# Serial-Basic-CH340C.net
KiCad netlist of a schematic drawn in EAGLE
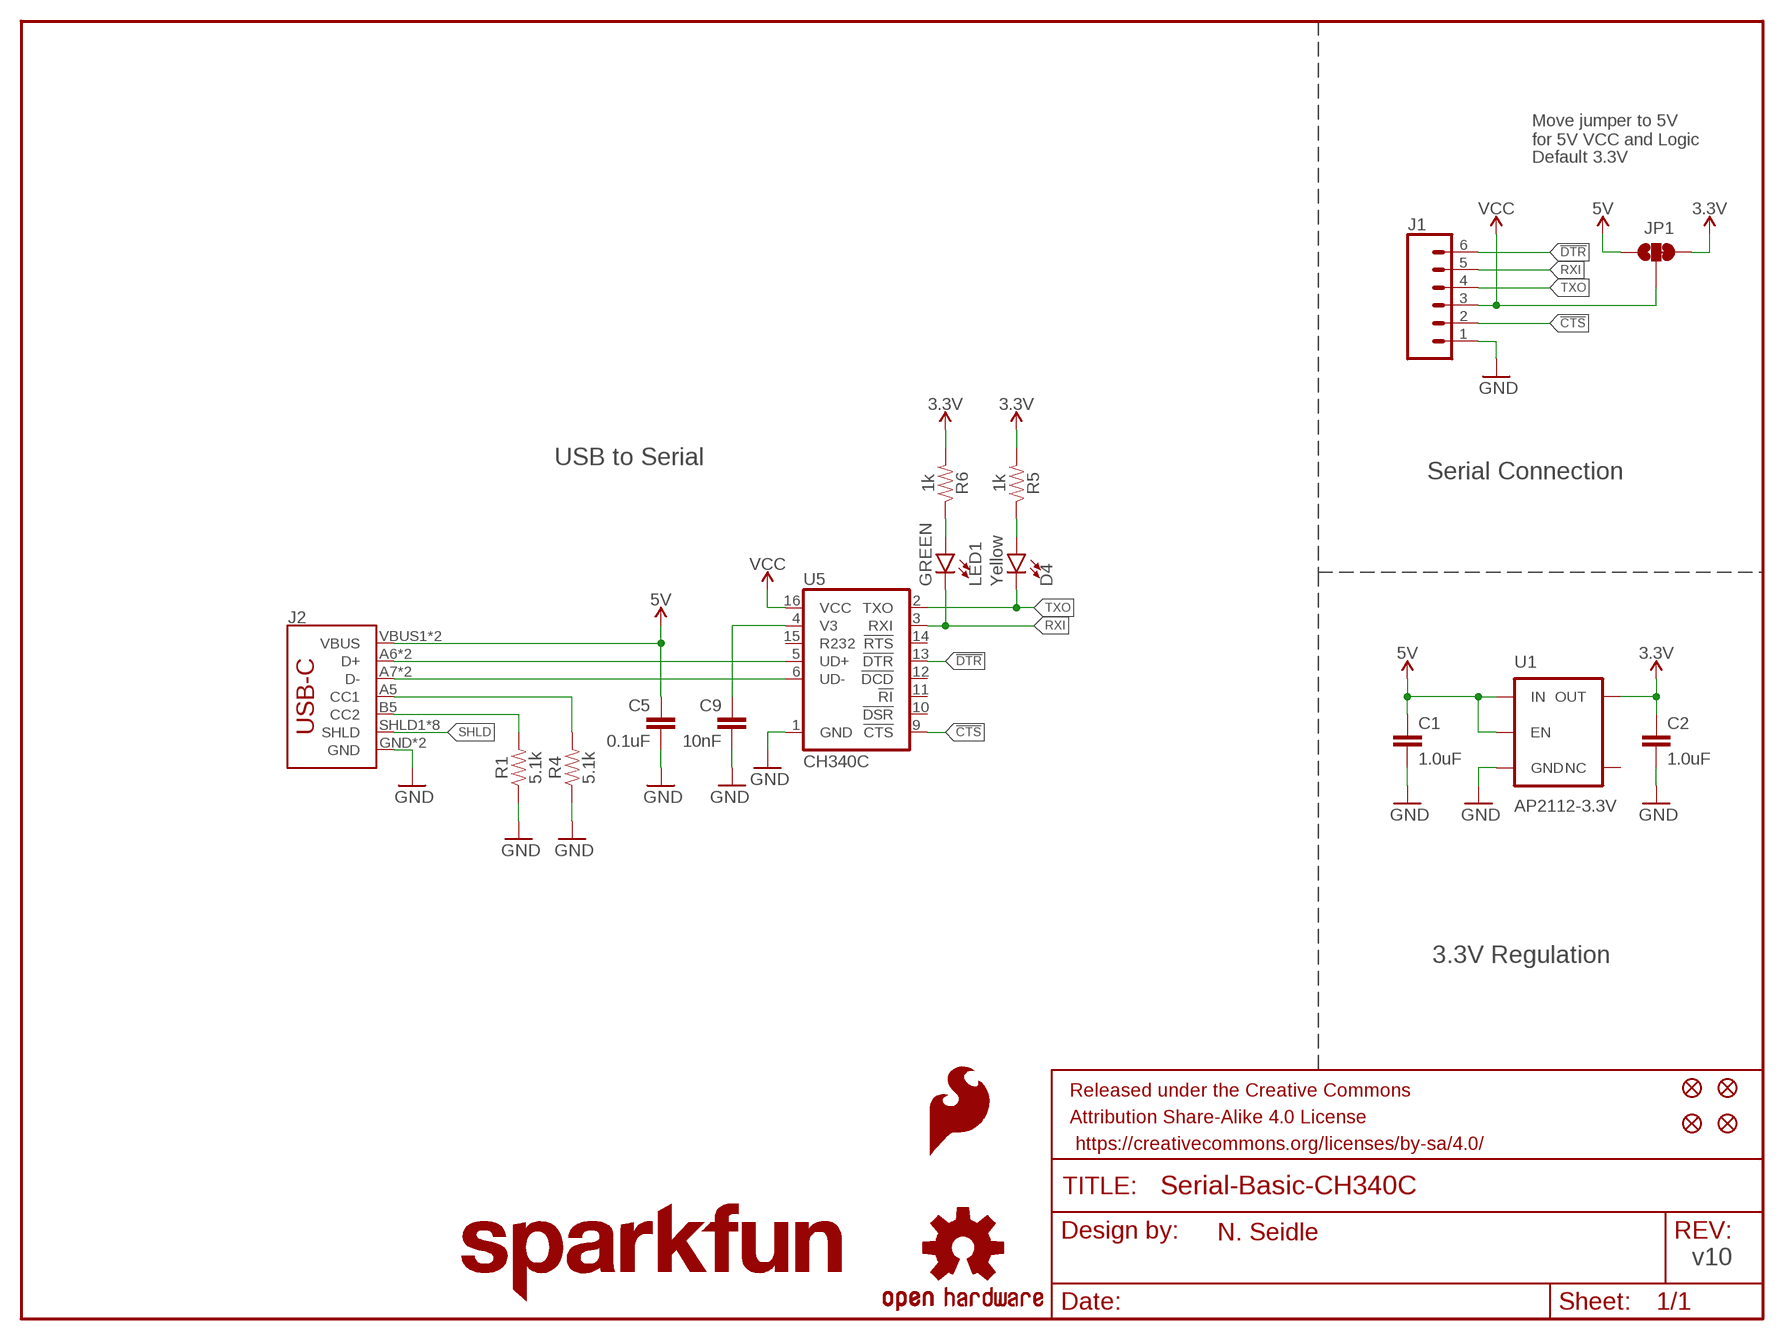
[diagram p0: schematic, sheet 1]

(export (version "E")
  (design (tool "Eeschema 10.0.6"))
  (components
    (comp (ref "C1")
      (value "1.0uF")
      (footprint "eagle-import:0603")
      (libsource (lib "eagle-import") (part "1.0UF-0603-16V-10%"))
    )
    (comp (ref "C2")
      (value "1.0uF")
      (footprint "eagle-import:0603")
      (libsource (lib "eagle-import") (part "1.0UF-0603-16V-10%"))
    )
    (comp (ref "C5")
      (value "0.1uF")
      (footprint "eagle-import:0603")
      (libsource (lib "eagle-import") (part "0.1UF-0603-25V-(+80/-20%)"))
    )
    (comp (ref "C9")
      (value "10nF")
      (footprint "eagle-import:0603")
      (libsource (lib "eagle-import") (part "10NF-0603-50V-10%"))
    )
    (comp (ref "D4")
      (value "Yellow")
      (footprint "eagle-import:LED-0603")
      (libsource (lib "eagle-import") (part "LED-YELLOW0603"))
    )
    (comp (ref "FRAME1")
      (value "FRAME-LETTER")
      (footprint "eagle-import:CREATIVE_COMMONS")
      (libsource (lib "eagle-import") (part "FRAME-LETTER"))
    )
    (comp (ref "J1")
      (value "CONN_06SMD-FEMALE-V2")
      (footprint "eagle-import:1X06-SMD-FEMALE")
      (libsource (lib "eagle-import") (part "CONN_06SMD-FEMALE-V2"))
    )
    (comp (ref "J2")
      (value "USB_C16PIN")
      (footprint "eagle-import:USB-C-16P")
      (libsource (lib "eagle-import") (part "USB_C16PIN"))
    )
    (comp (ref "JP1")
      (value "JUMPER-SMT_3_1-NC_TRACE_SILK")
      (footprint "eagle-import:SMT-JUMPER_3_1-NC_TRACE_SILK")
      (libsource (lib "eagle-import") (part "JUMPER-SMT_3_1-NC_TRACE_SILK"))
    )
    (comp (ref "JP3")
      (value "FIDUCIAL1X2")
      (footprint "eagle-import:FIDUCIAL-1X2")
      (libsource (lib "eagle-import") (part "FIDUCIAL1X2"))
    )
    (comp (ref "JP4")
      (value "FIDUCIAL1X2")
      (footprint "eagle-import:FIDUCIAL-1X2")
      (libsource (lib "eagle-import") (part "FIDUCIAL1X2"))
    )
    (comp (ref "JP5")
      (value "FIDUCIAL1X2")
      (footprint "eagle-import:FIDUCIAL-1X2")
      (libsource (lib "eagle-import") (part "FIDUCIAL1X2"))
    )
    (comp (ref "JP6")
      (value "FIDUCIAL1X2")
      (footprint "eagle-import:FIDUCIAL-1X2")
      (libsource (lib "eagle-import") (part "FIDUCIAL1X2"))
    )
    (comp (ref "LED1")
      (value "GREEN")
      (footprint "eagle-import:LED-0603")
      (libsource (lib "eagle-import") (part "LED-GREEN0603"))
    )
    (comp (ref "LOGO1")
      (value "OSHW-LOGOS")
      (footprint "eagle-import:OSHW-LOGO-S")
      (libsource (lib "eagle-import") (part "OSHW-LOGOS"))
    )
    (comp (ref "LOGO2")
      (value "SFE_LOGO_FLAME.1_INCH")
      (footprint "eagle-import:SFE_LOGO_FLAME_.1")
      (libsource (lib "eagle-import") (part "SFE_LOGO_FLAME.1_INCH"))
    )
    (comp (ref "LOGO3")
      (value "SFE_LOGO_NAME.1_INCH")
      (footprint "eagle-import:SFE_LOGO_NAME_.1")
      (libsource (lib "eagle-import") (part "SFE_LOGO_NAME.1_INCH"))
    )
    (comp (ref "R1")
      (value "5.1k")
      (footprint "eagle-import:0603")
      (libsource (lib "eagle-import") (part "5.1KOHM5.1KOHM-0603-1/10W-1%"))
    )
    (comp (ref "R4")
      (value "5.1k")
      (footprint "eagle-import:0603")
      (libsource (lib "eagle-import") (part "5.1KOHM5.1KOHM-0603-1/10W-1%"))
    )
    (comp (ref "R5")
      (value "1k")
      (footprint "eagle-import:0603")
      (libsource (lib "eagle-import") (part "1KOHM-0603-1/10W-1%"))
    )
    (comp (ref "R6")
      (value "1k")
      (footprint "eagle-import:0603")
      (libsource (lib "eagle-import") (part "1KOHM-0603-1/10W-1%"))
    )
    (comp (ref "U1")
      (value "AP2112-3.3V")
      (footprint "eagle-import:SOT23-5")
      (libsource (lib "eagle-import") (part "V_REG_AP2112K-3.3V"))
    )
    (comp (ref "U5")
      (value "CH340C")
      (footprint "eagle-import:SO016")
      (libsource (lib "eagle-import") (part "CH340C"))
    )
  )
  (nets
    (net (code "1") (name "/~{CTS}") (class "Default")
      (node (ref "J1") (pin "2") (pinfunction "2_2") (pintype "passive"))
      (node (ref "U5") (pin "9") (pinfunction "~{CTS}_9") (pintype "bidirectional"))
    )
    (net (code "2") (name "/~{DTR}") (class "Default")
      (node (ref "J1") (pin "6") (pinfunction "6_6") (pintype "passive"))
      (node (ref "U5") (pin "13") (pinfunction "~{DTR}_13") (pintype "bidirectional"))
    )
    (net (code "3") (name "3.3V") (class "Default")
      (node (ref "C2") (pin "1") (pinfunction "1_1") (pintype "passive"))
      (node (ref "JP1") (pin "3") (pinfunction "3_3") (pintype "passive"))
      (node (ref "R5") (pin "2") (pinfunction "2_2") (pintype "passive"))
      (node (ref "R6") (pin "2") (pinfunction "2_2") (pintype "passive"))
      (node (ref "U1") (pin "5") (pinfunction "OUT_5") (pintype "passive"))
    )
    (net (code "4") (name "5V") (class "Default")
      (node (ref "C1") (pin "1") (pinfunction "1_1") (pintype "passive"))
      (node (ref "C5") (pin "1") (pinfunction "1_1") (pintype "passive"))
      (node (ref "J2") (pin "VBUS1") (pinfunction "VBUS_VBUS1") (pintype "bidirectional"))
      (node (ref "J2") (pin "VBUS2") (pinfunction "VBUS_VBUS2") (pintype "bidirectional"))
      (node (ref "JP1") (pin "1") (pinfunction "1_1") (pintype "passive"))
      (node (ref "U1") (pin "1") (pinfunction "IN_1") (pintype "input"))
      (node (ref "U1") (pin "3") (pinfunction "EN_3") (pintype "input"))
    )
    (net (code "5") (name "GND") (class "Default")
      (node (ref "C1") (pin "2") (pinfunction "2_2") (pintype "passive"))
      (node (ref "C2") (pin "2") (pinfunction "2_2") (pintype "passive"))
      (node (ref "C5") (pin "2") (pinfunction "2_2") (pintype "passive"))
      (node (ref "C9") (pin "2") (pinfunction "2_2") (pintype "passive"))
      (node (ref "J1") (pin "1") (pinfunction "1_1") (pintype "passive"))
      (node (ref "J2") (pin "GND") (pinfunction "GND_GND") (pintype "bidirectional"))
      (node (ref "J2") (pin "GND2") (pinfunction "GND_GND2") (pintype "bidirectional"))
      (node (ref "R1") (pin "1") (pinfunction "1_1") (pintype "passive"))
      (node (ref "R4") (pin "1") (pinfunction "1_1") (pintype "passive"))
      (node (ref "U1") (pin "2") (pinfunction "GND_2") (pintype "input"))
      (node (ref "U5") (pin "1") (pinfunction "GND_1") (pintype "bidirectional"))
    )
    (net (code "6") (name "Net-(D4-PadA)") (class "Default")
      (node (ref "D4") (pin "A") (pinfunction "A_A") (pintype "passive"))
      (node (ref "R5") (pin "1") (pinfunction "1_1") (pintype "passive"))
    )
    (net (code "7") (name "Net-(J2-CC1)") (class "Default")
      (node (ref "J2") (pin "A5") (pinfunction "CC1_A5") (pintype "bidirectional"))
      (node (ref "R4") (pin "2") (pinfunction "2_2") (pintype "passive"))
    )
    (net (code "8") (name "Net-(J2-CC2)") (class "Default")
      (node (ref "J2") (pin "B5") (pinfunction "CC2_B5") (pintype "bidirectional"))
      (node (ref "R1") (pin "2") (pinfunction "2_2") (pintype "passive"))
    )
    (net (code "9") (name "Net-(LED1-PadA)") (class "Default")
      (node (ref "LED1") (pin "A") (pinfunction "A_A") (pintype "passive"))
      (node (ref "R6") (pin "1") (pinfunction "1_1") (pintype "passive"))
    )
    (net (code "10") (name "Net-(U5-UD+)") (class "Default")
      (node (ref "J2") (pin "A6") (pinfunction "D+_A6") (pintype "bidirectional"))
      (node (ref "J2") (pin "B6") (pinfunction "D+_B6") (pintype "bidirectional"))
      (node (ref "U5") (pin "5") (pinfunction "UD+_5") (pintype "bidirectional"))
    )
    (net (code "11") (name "Net-(U5-UD-)") (class "Default")
      (node (ref "J2") (pin "A7") (pinfunction "D-_A7") (pintype "bidirectional"))
      (node (ref "J2") (pin "B7") (pinfunction "D-_B7") (pintype "bidirectional"))
      (node (ref "U5") (pin "6") (pinfunction "UD-_6") (pintype "bidirectional"))
    )
    (net (code "12") (name "Net-(U5-V3)") (class "Default")
      (node (ref "C9") (pin "1") (pinfunction "1_1") (pintype "passive"))
      (node (ref "U5") (pin "4") (pinfunction "V3_4") (pintype "bidirectional"))
    )
    (net (code "13") (name "RXI") (class "Default")
      (node (ref "J1") (pin "5") (pinfunction "5_5") (pintype "passive"))
      (node (ref "LED1") (pin "C") (pinfunction "C_C") (pintype "passive"))
      (node (ref "U5") (pin "3") (pinfunction "RXI_3") (pintype "bidirectional"))
    )
    (net (code "14") (name "SHLD") (class "Default")
      (node (ref "J2") (pin "SHLD1") (pinfunction "SHLD_SHLD1") (pintype "bidirectional"))
      (node (ref "J2") (pin "SHLD2") (pinfunction "SHLD_SHLD2") (pintype "bidirectional"))
      (node (ref "J2") (pin "SHLD3") (pinfunction "SHLD_SHLD3") (pintype "bidirectional"))
      (node (ref "J2") (pin "SHLD4") (pinfunction "SHLD_SHLD4") (pintype "bidirectional"))
      (node (ref "J2") (pin "SHLD5") (pinfunction "SHLD_SHLD5") (pintype "bidirectional"))
      (node (ref "J2") (pin "SHLD6") (pinfunction "SHLD_SHLD6") (pintype "bidirectional"))
      (node (ref "J2") (pin "SHLD7") (pinfunction "SHLD_SHLD7") (pintype "bidirectional"))
      (node (ref "J2") (pin "SHLD8") (pinfunction "SHLD_SHLD8") (pintype "bidirectional"))
    )
    (net (code "15") (name "TXO") (class "Default")
      (node (ref "D4") (pin "C") (pinfunction "C_C") (pintype "passive"))
      (node (ref "J1") (pin "4") (pinfunction "4_4") (pintype "passive"))
      (node (ref "U5") (pin "2") (pinfunction "TXO_2") (pintype "bidirectional"))
    )
    (net (code "16") (name "VCC") (class "Default")
      (node (ref "J1") (pin "3") (pinfunction "3_3") (pintype "passive"))
      (node (ref "JP1") (pin "2") (pinfunction "2_2") (pintype "passive"))
      (node (ref "U5") (pin "16") (pinfunction "VCC_16") (pintype "bidirectional"))
    )
    (net (code "17") (name "unconnected-(U1-NC-Pad4)") (class "Default")
      (node (ref "U1") (pin "4") (pinfunction "NC_4") (pintype "input"))
    )
    (net (code "18") (name "unconnected-(U5-R232-Pad15)") (class "Default")
      (node (ref "U5") (pin "15") (pinfunction "R232_15") (pintype "bidirectional"))
    )
    (net (code "19") (name "unconnected-(U5-~{DCD}-Pad12)") (class "Default")
      (node (ref "U5") (pin "12") (pinfunction "~{DCD}_12") (pintype "bidirectional"))
    )
    (net (code "20") (name "unconnected-(U5-~{DSR}-Pad10)") (class "Default")
      (node (ref "U5") (pin "10") (pinfunction "~{DSR}_10") (pintype "bidirectional"))
    )
    (net (code "21") (name "unconnected-(U5-~{RI}-Pad11)") (class "Default")
      (node (ref "U5") (pin "11") (pinfunction "~{RI}_11") (pintype "bidirectional"))
    )
    (net (code "22") (name "unconnected-(U5-~{RTS}-Pad14)") (class "Default")
      (node (ref "U5") (pin "14") (pinfunction "~{RTS}_14") (pintype "bidirectional"))
    )
  )
)
